# kondratchenko_telemetry_board.net
KiCad netlist of a schematic drawn in Altium Designer
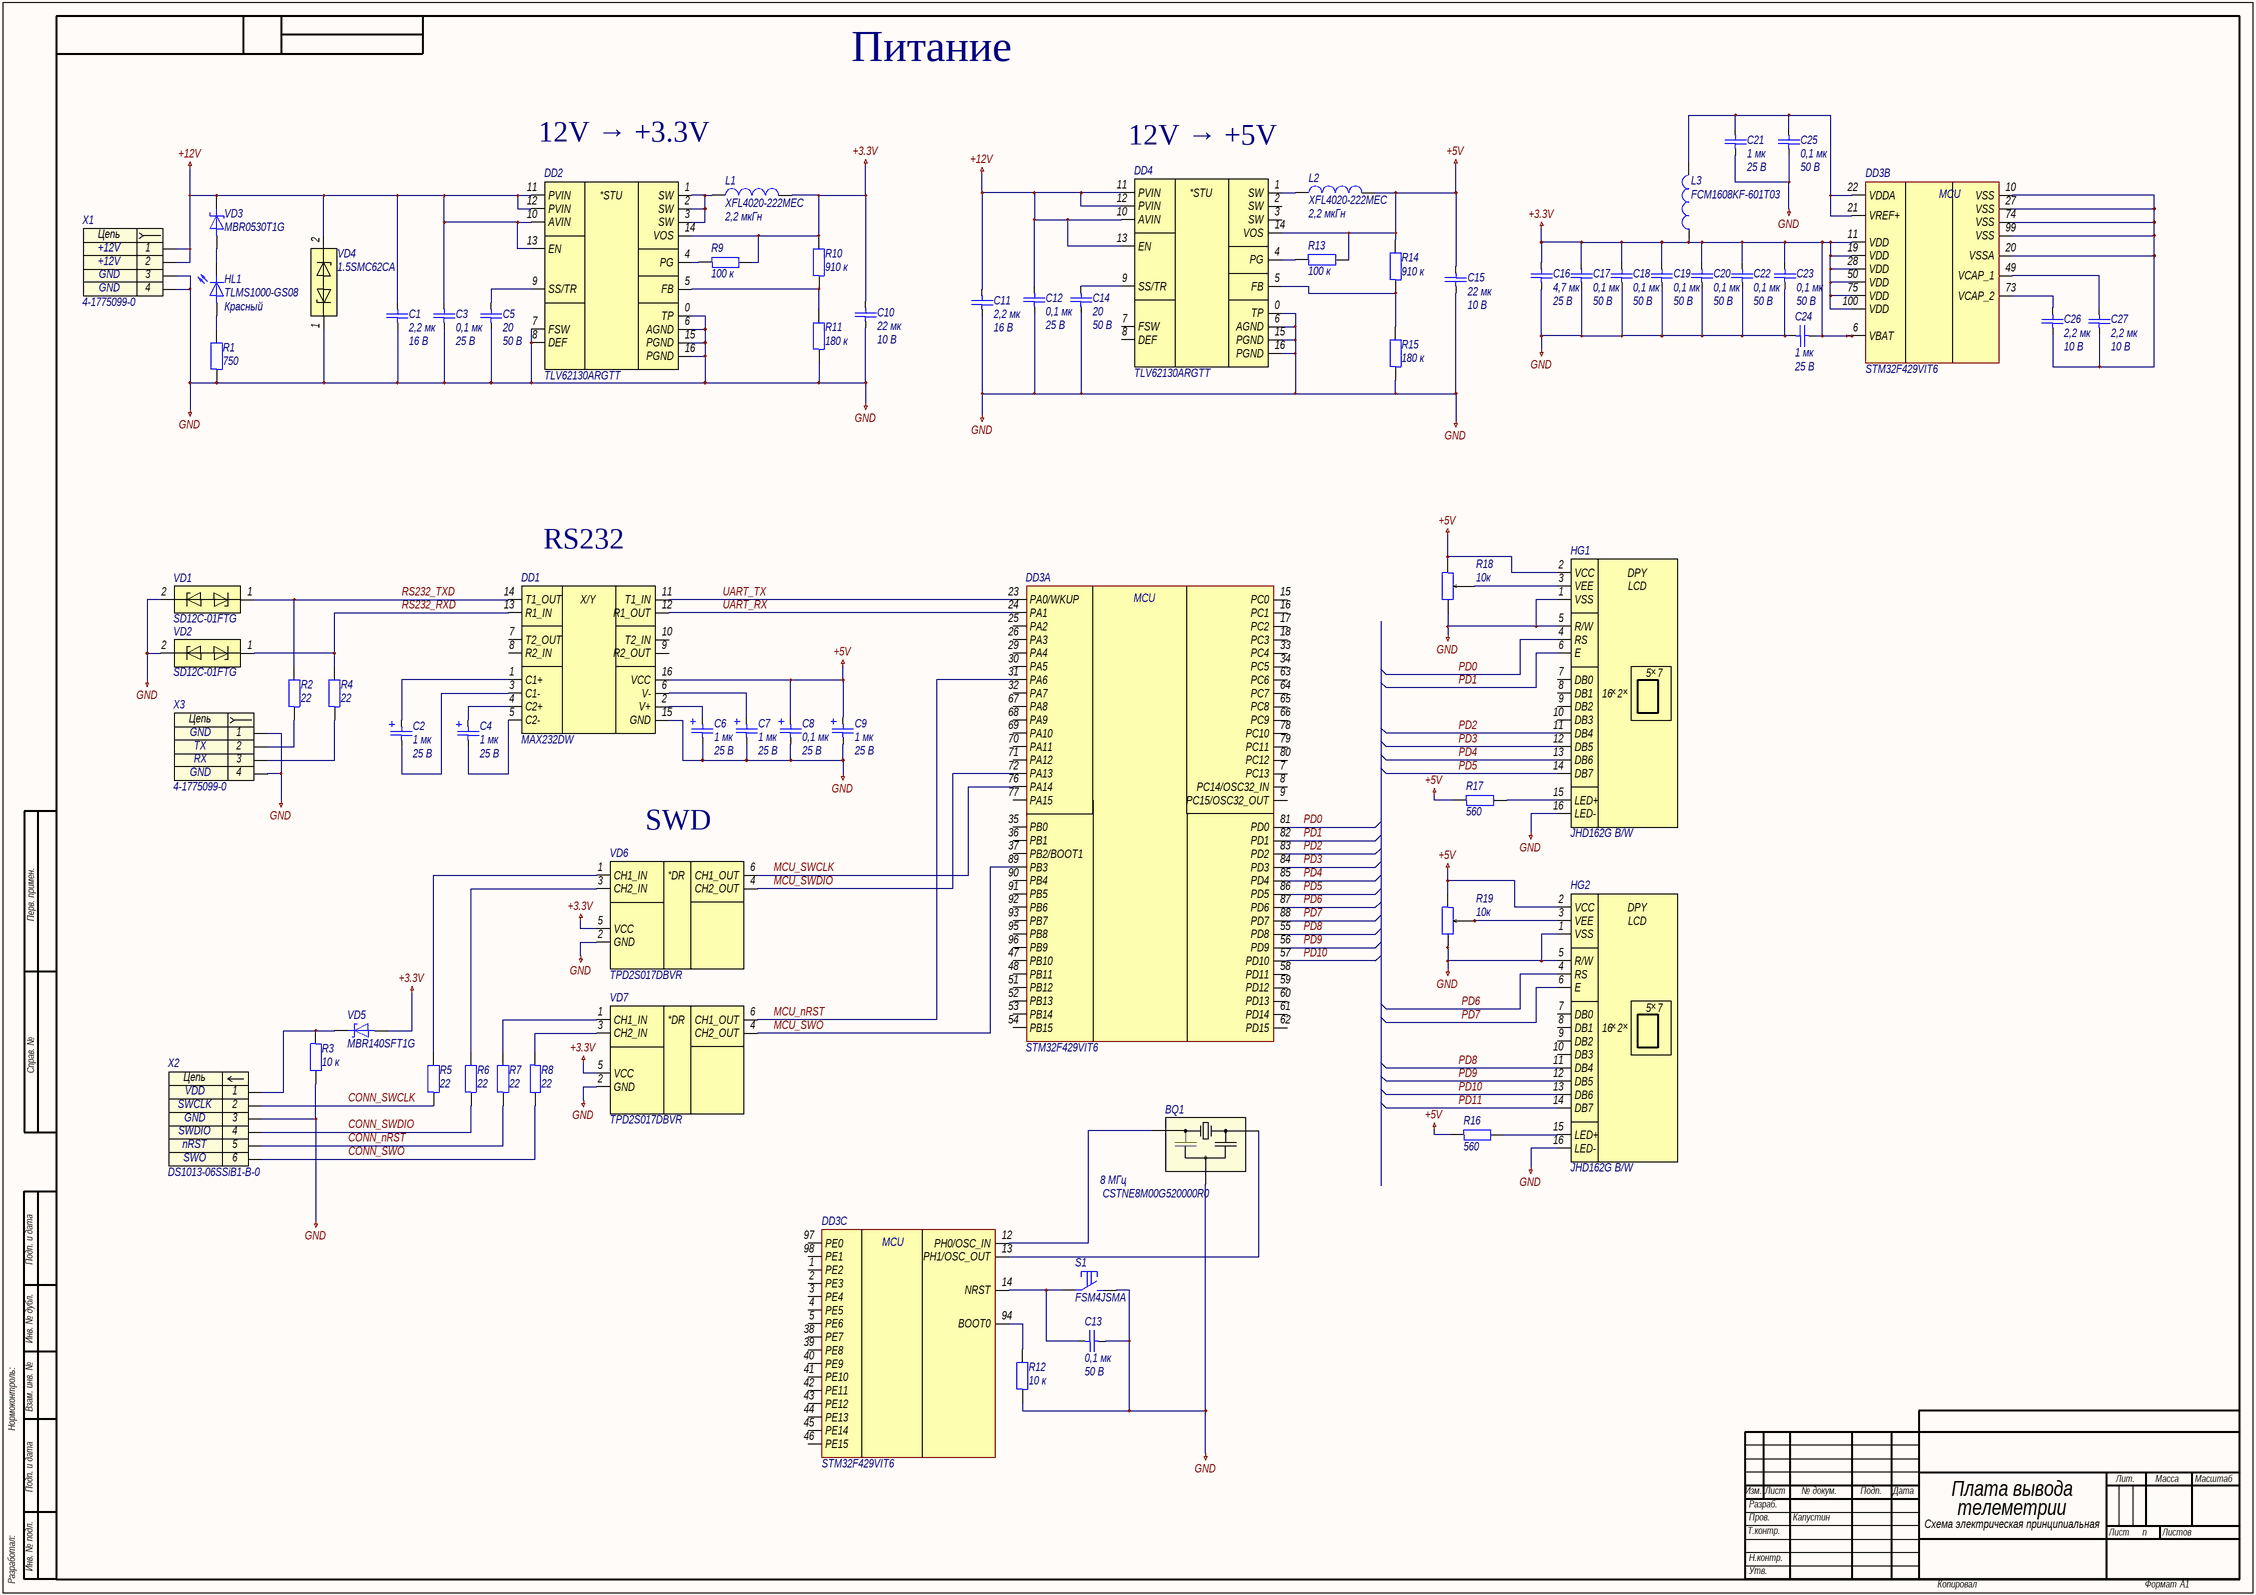
[diagram p0: kondratchenko_telemetry_board.SchDoc]

(export (version "E")
  (design (tool "Eeschema 10.0.6"))
  (components
    (comp (ref "BQ1")
      (value "CSTNE8M00G520000R0")
      (footprint "CSTCE-3-P120-320X130X70")
      (description "=Описание")
      (fields (field (name "ЧАСТОТA") "8 МГц"))
      (libsource (lib "Database_Students") (part "CSTNE8M00G520000R0"))
    )
    (comp (ref "C1")
      (value "2,2 мк")
      (footprint "C0603")
      (description "=Описание")
      (fields (field (name "НАПРЯЖЕНИЕ") "16 В"))
      (libsource (lib "Database_Students") (part "CAPACITOR-NONPOLAR"))
    )
    (comp (ref "C2")
      (value "1 мк")
      (footprint "C3216-18")
      (description "=Описание")
      (fields (field (name "НАПРЯЖЕНИЕ") "25 В"))
      (libsource (lib "Database_Students") (part "CAPACITOR-POLAR"))
    )
    (comp (ref "C3")
      (value "0,1 мк")
      (footprint "C0603")
      (description "=Описание")
      (fields (field (name "НАПРЯЖЕНИЕ") "25 В"))
      (libsource (lib "Database_Students") (part "CAPACITOR-NONPOLAR"))
    )
    (comp (ref "C4")
      (value "1 мк")
      (footprint "C3216-18")
      (description "=Описание")
      (fields (field (name "НАПРЯЖЕНИЕ") "25 В"))
      (libsource (lib "Database_Students") (part "CAPACITOR-POLAR"))
    )
    (comp (ref "C5")
      (value "20")
      (footprint "C0603")
      (description "=Описание")
      (fields (field (name "НАПРЯЖЕНИЕ") "50 В"))
      (libsource (lib "Database_Students") (part "CAPACITOR-NONPOLAR"))
    )
    (comp (ref "C6")
      (value "1 мк")
      (footprint "C3216-18")
      (description "=Описание")
      (fields (field (name "НАПРЯЖЕНИЕ") "25 В"))
      (libsource (lib "Database_Students") (part "CAPACITOR-POLAR"))
    )
    (comp (ref "C7")
      (value "1 мк")
      (footprint "C3216-18")
      (description "=Описание")
      (fields (field (name "НАПРЯЖЕНИЕ") "25 В"))
      (libsource (lib "Database_Students") (part "CAPACITOR-POLAR"))
    )
    (comp (ref "C8")
      (value "0,1 мк")
      (footprint "C3216-18")
      (description "=Описание")
      (fields (field (name "НАПРЯЖЕНИЕ") "25 В"))
      (libsource (lib "Database_Students") (part "CAPACITOR-POLAR"))
    )
    (comp (ref "C9")
      (value "1 мк")
      (footprint "C3216-18")
      (description "=Описание")
      (fields (field (name "НАПРЯЖЕНИЕ") "25 В"))
      (libsource (lib "Database_Students") (part "CAPACITOR-POLAR"))
    )
    (comp (ref "C10")
      (value "22 мк")
      (footprint "C1206")
      (description "=Описание")
      (fields (field (name "НАПРЯЖЕНИЕ") "10 В"))
      (libsource (lib "Database_Students") (part "CAPACITOR-NONPOLAR"))
    )
    (comp (ref "C11")
      (value "2,2 мк")
      (footprint "C0603")
      (description "=Описание")
      (fields (field (name "НАПРЯЖЕНИЕ") "16 В"))
      (libsource (lib "Database_Students") (part "CAPACITOR-NONPOLAR"))
    )
    (comp (ref "C12")
      (value "0,1 мк")
      (footprint "C0603")
      (description "=Описание")
      (fields (field (name "НАПРЯЖЕНИЕ") "25 В"))
      (libsource (lib "Database_Students") (part "CAPACITOR-NONPOLAR"))
    )
    (comp (ref "C13")
      (value "0,1 мк")
      (footprint "C0603")
      (description "=Описание")
      (fields (field (name "НАПРЯЖЕНИЕ") "50 В"))
      (libsource (lib "Database_Students") (part "CAPACITOR-NONPOLAR"))
    )
    (comp (ref "C14")
      (value "20")
      (footprint "C0603")
      (description "=Описание")
      (fields (field (name "НАПРЯЖЕНИЕ") "50 В"))
      (libsource (lib "Database_Students") (part "CAPACITOR-NONPOLAR"))
    )
    (comp (ref "C15")
      (value "22 мк")
      (footprint "C1206")
      (description "=Описание")
      (fields (field (name "НАПРЯЖЕНИЕ") "10 В"))
      (libsource (lib "Database_Students") (part "CAPACITOR-NONPOLAR"))
    )
    (comp (ref "C16")
      (value "4,7 мк")
      (footprint "C0603")
      (description "=Описание")
      (fields (field (name "НАПРЯЖЕНИЕ") "25 В"))
      (libsource (lib "Database_Students") (part "CAPACITOR-NONPOLAR"))
    )
    (comp (ref "C17")
      (value "0,1 мк")
      (footprint "C0603")
      (description "=Описание")
      (fields (field (name "НАПРЯЖЕНИЕ") "50 В"))
      (libsource (lib "Database_Students") (part "CAPACITOR-NONPOLAR"))
    )
    (comp (ref "C18")
      (value "0,1 мк")
      (footprint "C0603")
      (description "=Описание")
      (fields (field (name "НАПРЯЖЕНИЕ") "50 В"))
      (libsource (lib "Database_Students") (part "CAPACITOR-NONPOLAR"))
    )
    (comp (ref "C19")
      (value "0,1 мк")
      (footprint "C0603")
      (description "=Описание")
      (fields (field (name "НАПРЯЖЕНИЕ") "50 В"))
      (libsource (lib "Database_Students") (part "CAPACITOR-NONPOLAR"))
    )
    (comp (ref "C20")
      (value "0,1 мк")
      (footprint "C0603")
      (description "=Описание")
      (fields (field (name "НАПРЯЖЕНИЕ") "50 В"))
      (libsource (lib "Database_Students") (part "CAPACITOR-NONPOLAR"))
    )
    (comp (ref "C21")
      (value "1 мк")
      (footprint "C0603")
      (description "=Описание")
      (fields (field (name "НАПРЯЖЕНИЕ") "25 В"))
      (libsource (lib "Database_Students") (part "CAPACITOR-NONPOLAR"))
    )
    (comp (ref "C22")
      (value "0,1 мк")
      (footprint "C0603")
      (description "=Описание")
      (fields (field (name "НАПРЯЖЕНИЕ") "50 В"))
      (libsource (lib "Database_Students") (part "CAPACITOR-NONPOLAR"))
    )
    (comp (ref "C23")
      (value "0,1 мк")
      (footprint "C0603")
      (description "=Описание")
      (fields (field (name "НАПРЯЖЕНИЕ") "50 В"))
      (libsource (lib "Database_Students") (part "CAPACITOR-NONPOLAR"))
    )
    (comp (ref "C24")
      (value "1 мк")
      (footprint "C0603")
      (description "=Описание")
      (fields (field (name "НАПРЯЖЕНИЕ") "25 В"))
      (libsource (lib "Database_Students") (part "CAPACITOR-NONPOLAR"))
    )
    (comp (ref "C25")
      (value "0,1 мк")
      (footprint "C0603")
      (description "=Описание")
      (fields (field (name "НАПРЯЖЕНИЕ") "50 В"))
      (libsource (lib "Database_Students") (part "CAPACITOR-NONPOLAR"))
    )
    (comp (ref "C26")
      (value "2,2 мк")
      (footprint "C0603")
      (description "=Описание")
      (fields (field (name "НАПРЯЖЕНИЕ") "10 В"))
      (libsource (lib "Database_Students") (part "CAPACITOR-NONPOLAR"))
    )
    (comp (ref "C27")
      (value "2,2 мк")
      (footprint "C0603")
      (description "=Описание")
      (fields (field (name "НАПРЯЖЕНИЕ") "10 В"))
      (libsource (lib "Database_Students") (part "CAPACITOR-NONPOLAR"))
    )
    (comp (ref "DD1")
      (value "MAX232DW")
      (footprint "SOIC-16-P127-1030X750X265-L84X41")
      (description "=Описание")
      (libsource (lib "Database_Students") (part "MAX232DW"))
    )
    (comp (ref "DD2")
      (value "TLV62130ARGTT")
      (footprint "WQFN-16-P50-300X300X100-L40X24-T168X168")
      (description "=Описание")
      (libsource (lib "Database_Students") (part "TLV62130ARGTT"))
    )
    (comp (ref "DD3")
      (value "STM32F429VIT6")
      (footprint "LQFP-100-P50-1400X1400X160-L60X22")
      (description "=Описание")
      (libsource (lib "") (part "STM32F429VIT6_1"))
    )
    (comp (ref "DD4")
      (value "TLV62130ARGTT")
      (footprint "WQFN-16-P50-300X300X100-L40X24-T168X168")
      (description "=Описание")
      (libsource (lib "Database_Students") (part "TLV62130ARGTT"))
    )
    (comp (ref "HG1")
      (value "JHD162G B/W")
      (footprint "JHD162G B/W")
      (description "=Описание")
      (libsource (lib "Database_Students") (part "JHD162G B/W"))
    )
    (comp (ref "HG2")
      (value "JHD162G B/W")
      (footprint "JHD162G B/W")
      (description "=Описание")
      (libsource (lib "Database_Students") (part "JHD162G B/W"))
    )
    (comp (ref "HL1")
      (value "TLMS1000-GS08")
      (footprint "HL0603")
      (description "=Описание")
      (fields (field (name "ЦВЕТ") "Красный"))
      (libsource (lib "Database_Students") (part "LED-COMMON"))
    )
    (comp (ref "L1")
      (value "XFL4020-222MEC")
      (footprint "XFL-2-400X400X210")
      (description "=Описание")
      (fields (field (name "ИНДУКТИВНОСТЬ") "2,2 мкГн"))
      (libsource (lib "Database_Students") (part "INDUCTOR-COMMON"))
    )
    (comp (ref "L2")
      (value "XFL4020-222MEC")
      (footprint "XFL-2-400X400X210")
      (description "=Описание")
      (fields (field (name "ИНДУКТИВНОСТЬ") "2,2 мкГн"))
      (libsource (lib "Database_Students") (part "INDUCTOR-COMMON"))
    )
    (comp (ref "L3")
      (value "FCM1608KF-601T03")
      (footprint "FCM-2-0603")
      (description "=Описание")
      (libsource (lib "Database_Students") (part "FERRITE-BEAD"))
    )
    (comp (ref "R1")
      (value "750")
      (footprint "R0603")
      (description "=Описание")
      (libsource (lib "Database_Students") (part "RESISTOR-COMMON"))
    )
    (comp (ref "R2")
      (value "22")
      (footprint "R0603")
      (description "=Описание")
      (libsource (lib "Database_Students") (part "RESISTOR-COMMON"))
    )
    (comp (ref "R3")
      (value "10 к")
      (footprint "R0603")
      (description "=Описание")
      (libsource (lib "Database_Students") (part "RESISTOR-COMMON"))
    )
    (comp (ref "R4")
      (value "22")
      (footprint "R0603")
      (description "=Описание")
      (libsource (lib "Database_Students") (part "RESISTOR-COMMON"))
    )
    (comp (ref "R5")
      (value "22")
      (footprint "R0603")
      (description "=Описание")
      (libsource (lib "Database_Students") (part "RESISTOR-COMMON"))
    )
    (comp (ref "R6")
      (value "22")
      (footprint "R0603")
      (description "=Описание")
      (libsource (lib "Database_Students") (part "RESISTOR-COMMON"))
    )
    (comp (ref "R7")
      (value "22")
      (footprint "R0603")
      (description "=Описание")
      (libsource (lib "Database_Students") (part "RESISTOR-COMMON"))
    )
    (comp (ref "R8")
      (value "22")
      (footprint "R0603")
      (description "=Описание")
      (libsource (lib "Database_Students") (part "RESISTOR-COMMON"))
    )
    (comp (ref "R9")
      (value "100 к")
      (footprint "R0603")
      (description "=Описание")
      (libsource (lib "Database_Students") (part "RESISTOR-COMMON"))
    )
    (comp (ref "R10")
      (value "910 к")
      (footprint "R0603")
      (description "=Описание")
      (libsource (lib "Database_Students") (part "RESISTOR-COMMON"))
    )
    (comp (ref "R11")
      (value "180 к")
      (footprint "R0603")
      (description "=Описание")
      (libsource (lib "Database_Students") (part "RESISTOR-COMMON"))
    )
    (comp (ref "R12")
      (value "10 к")
      (footprint "R0603")
      (description "=Описание")
      (libsource (lib "Database_Students") (part "RESISTOR-COMMON"))
    )
    (comp (ref "R13")
      (value "100 к")
      (footprint "R0603")
      (description "=Описание")
      (libsource (lib "Database_Students") (part "RESISTOR-COMMON"))
    )
    (comp (ref "R14")
      (value "910 к")
      (footprint "R0603")
      (description "=Описание")
      (libsource (lib "Database_Students") (part "RESISTOR-COMMON"))
    )
    (comp (ref "R15")
      (value "180 к")
      (footprint "R0603")
      (description "=Описание")
      (libsource (lib "Database_Students") (part "RESISTOR-COMMON"))
    )
    (comp (ref "R16")
      (value "560")
      (footprint "R0603")
      (description "=Описание")
      (libsource (lib "Database_Students") (part "RESISTOR-COMMON"))
    )
    (comp (ref "R17")
      (value "560")
      (footprint "R0603")
      (description "=Описание")
      (libsource (lib "Database_Students") (part "RESISTOR-COMMON"))
    )
    (comp (ref "R18")
      (value "10к")
      (footprint "R3362")
      (description "=Описание")
      (libsource (lib "Database_Students") (part "TRIMMER-COMMON"))
    )
    (comp (ref "R19")
      (value "10к")
      (footprint "R3362")
      (description "=Описание")
      (libsource (lib "Database_Students") (part "TRIMMER-COMMON"))
    )
    (comp (ref "S1")
      (value "FSM4JSMA")
      (footprint "FSM4JSMA")
      (description "=Описание")
      (libsource (lib "Database_Students") (part "BUTTON"))
    )
    (comp (ref "VD1")
      (value "SD12C-01FTG")
      (footprint "SOD-323-257X130X114")
      (description "=Описание")
      (libsource (lib "") (part "ZENER-BI-DIRECTIONAL_1"))
    )
    (comp (ref "VD2")
      (value "SD12C-01FTG")
      (footprint "SOD-323-257X130X114")
      (description "=Описание")
      (libsource (lib "") (part "ZENER-BI-DIRECTIONAL_1"))
    )
    (comp (ref "VD3")
      (value "MBR0530T1G")
      (footprint "SOD-123-368X160X135")
      (description "=Описание")
      (libsource (lib "Database_Students") (part "DIODE-SCHOTTKY"))
    )
    (comp (ref "VD4")
      (value "1.5SMC62CA")
      (footprint "DO-214AB-790X590X262")
      (description "=Описание")
      (libsource (lib "Database_Students") (part "ZENER-BI-DIRECTIONAL"))
    )
    (comp (ref "VD5")
      (value "MBR140SFT1G")
      (footprint "SOD-123FL-370X165X98")
      (description "=Описание")
      (libsource (lib "Database_Students") (part "DIODE-SCHOTTKY"))
    )
    (comp (ref "VD6")
      (value "TPD2S017DBVR")
      (footprint "SOT-23-6-P95-290X280X145")
      (description "=Описание")
      (libsource (lib "Database_Students") (part "TPD2S017DBVR"))
    )
    (comp (ref "VD7")
      (value "TPD2S017DBVR")
      (footprint "SOT-23-6-P95-290X280X145")
      (description "=Описание")
      (libsource (lib "Database_Students") (part "TPD2S017DBVR"))
    )
    (comp (ref "X1")
      (value "4-1775099-0")
      (footprint "4-1775099-0")
      (description "=Описание")
      (libsource (lib "Database_Students") (part "HEADER-4-SCT"))
    )
    (comp (ref "X2")
      (value "DS1013-06SSiB1-B-0")
      (footprint "DS1013-06SSiB1-B-0")
      (description "=Описание")
      (libsource (lib "Database_Students") (part "HEADER-6-PLG"))
    )
    (comp (ref "X3")
      (value "4-1775099-0")
      (footprint "4-1775099-0")
      (description "=Описание")
      (libsource (lib "Database_Students") (part "HEADER-4-SCT"))
    )
  )
  (nets
    (net (code "1") (name "+3.3V") (class "Default")
      (node (ref "C10") (pin "1") (pinfunction "1_1") (pintype "passive"))
      (node (ref "C16") (pin "1") (pinfunction "1_1") (pintype "passive"))
      (node (ref "C17") (pin "1") (pinfunction "1_1") (pintype "passive"))
      (node (ref "C18") (pin "1") (pinfunction "1_1") (pintype "passive"))
      (node (ref "C19") (pin "1") (pinfunction "1_1") (pintype "passive"))
      (node (ref "C20") (pin "1") (pinfunction "1_1") (pintype "passive"))
      (node (ref "C22") (pin "1") (pinfunction "1_1") (pintype "passive"))
      (node (ref "C23") (pin "1") (pinfunction "1_1") (pintype "passive"))
      (node (ref "C24") (pin "1") (pinfunction "1_1") (pintype "passive"))
      (node (ref "DD2") (pin "14") (pinfunction "VOS_14") (pintype "passive"))
      (node (ref "DD3") (pin "100") (pinfunction "VDD_100") (pintype "passive"))
      (node (ref "DD3") (pin "11") (pinfunction "VDD_11") (pintype "passive"))
      (node (ref "DD3") (pin "19") (pinfunction "VDD_19") (pintype "passive"))
      (node (ref "DD3") (pin "28") (pinfunction "VDD_28") (pintype "passive"))
      (node (ref "DD3") (pin "50") (pinfunction "VDD_50") (pintype "passive"))
      (node (ref "DD3") (pin "6") (pinfunction "VBAT_6") (pintype "passive"))
      (node (ref "DD3") (pin "75") (pinfunction "VDD_75") (pintype "passive"))
      (node (ref "L1") (pin "2") (pinfunction "2_2") (pintype "passive"))
      (node (ref "L3") (pin "1") (pinfunction "1_1") (pintype "passive"))
      (node (ref "R10") (pin "2") (pinfunction "2_2") (pintype "passive"))
      (node (ref "R9") (pin "2") (pinfunction "2_2") (pintype "passive"))
      (node (ref "VD5") (pin "2") (pinfunction "2_2") (pintype "passive"))
      (node (ref "VD6") (pin "5") (pinfunction "VCC_5") (pintype "passive"))
      (node (ref "VD7") (pin "5") (pinfunction "VCC_5") (pintype "passive"))
    )
    (net (code "2") (name "+5V") (class "Default")
      (node (ref "C15") (pin "2") (pinfunction "2_2") (pintype "passive"))
      (node (ref "C8") (pin "1") (pinfunction "1_1") (pintype "passive"))
      (node (ref "C9") (pin "1") (pinfunction "1_1") (pintype "passive"))
      (node (ref "DD1") (pin "16") (pinfunction "VCC_16") (pintype "passive"))
      (node (ref "DD4") (pin "14") (pinfunction "VOS_14") (pintype "passive"))
      (node (ref "HG1") (pin "2") (pinfunction "VCC_2") (pintype "passive"))
      (node (ref "HG2") (pin "2") (pinfunction "VCC_2") (pintype "passive"))
      (node (ref "L2") (pin "2") (pinfunction "2_2") (pintype "passive"))
      (node (ref "R13") (pin "2") (pinfunction "2_2") (pintype "passive"))
      (node (ref "R14") (pin "2") (pinfunction "2_2") (pintype "passive"))
      (node (ref "R16") (pin "1") (pinfunction "1_1") (pintype "passive"))
      (node (ref "R17") (pin "1") (pinfunction "1_1") (pintype "passive"))
      (node (ref "R18") (pin "1") (pinfunction "1_1") (pintype "passive"))
      (node (ref "R19") (pin "1") (pinfunction "1_1") (pintype "passive"))
    )
    (net (code "3") (name "+12V") (class "Default")
      (node (ref "C1") (pin "1") (pinfunction "1_1") (pintype "passive"))
      (node (ref "C11") (pin "1") (pinfunction "1_1") (pintype "passive"))
      (node (ref "C12") (pin "1") (pinfunction "1_1") (pintype "passive"))
      (node (ref "C3") (pin "1") (pinfunction "1_1") (pintype "passive"))
      (node (ref "DD2") (pin "10") (pinfunction "AVIN_10") (pintype "passive"))
      (node (ref "DD2") (pin "11") (pinfunction "PVIN_11") (pintype "passive"))
      (node (ref "DD2") (pin "12") (pinfunction "PVIN_12") (pintype "passive"))
      (node (ref "DD2") (pin "13") (pinfunction "EN_13") (pintype "passive"))
      (node (ref "DD4") (pin "10") (pinfunction "AVIN_10") (pintype "passive"))
      (node (ref "DD4") (pin "11") (pinfunction "PVIN_11") (pintype "passive"))
      (node (ref "DD4") (pin "12") (pinfunction "PVIN_12") (pintype "passive"))
      (node (ref "DD4") (pin "13") (pinfunction "EN_13") (pintype "passive"))
      (node (ref "VD3") (pin "1") (pinfunction "1_1") (pintype "passive"))
      (node (ref "VD4") (pin "2") (pinfunction "2_2") (pintype "passive"))
      (node (ref "X1") (pin "1") (pinfunction "1_1") (pintype "passive"))
      (node (ref "X1") (pin "2") (pinfunction "2_2") (pintype "passive"))
    )
    (net (code "4") (name "/CONN_SWCLK") (class "Default")
      (node (ref "R5") (pin "1") (pinfunction "1_1") (pintype "passive"))
      (node (ref "X2") (pin "2") (pinfunction "2_2") (pintype "passive"))
    )
    (net (code "5") (name "/CONN_SWDIO") (class "Default")
      (node (ref "R6") (pin "1") (pinfunction "1_1") (pintype "passive"))
      (node (ref "X2") (pin "4") (pinfunction "4_4") (pintype "passive"))
    )
    (net (code "6") (name "/CONN_SWO") (class "Default")
      (node (ref "R8") (pin "2") (pinfunction "2_2") (pintype "passive"))
      (node (ref "X2") (pin "6") (pinfunction "6_6") (pintype "passive"))
    )
    (net (code "7") (name "/CONN_nRST") (class "Default")
      (node (ref "R7") (pin "1") (pinfunction "1_1") (pintype "passive"))
      (node (ref "X2") (pin "5") (pinfunction "5_5") (pintype "passive"))
    )
    (net (code "8") (name "/MCU_SWCLK") (class "Default")
      (node (ref "DD3") (pin "76") (pinfunction "PA14_76") (pintype "passive"))
      (node (ref "VD6") (pin "6") (pinfunction "CH1_OUT_6") (pintype "passive"))
    )
    (net (code "9") (name "/MCU_SWDIO") (class "Default")
      (node (ref "DD3") (pin "72") (pinfunction "PA13_72") (pintype "passive"))
      (node (ref "VD6") (pin "4") (pinfunction "CH2_OUT_4") (pintype "passive"))
    )
    (net (code "10") (name "/MCU_SWO") (class "Default")
      (node (ref "DD3") (pin "89") (pinfunction "PB3_89") (pintype "passive"))
      (node (ref "VD7") (pin "4") (pinfunction "CH2_OUT_4") (pintype "passive"))
    )
    (net (code "11") (name "/MCU_nRST") (class "Default")
      (node (ref "DD3") (pin "31") (pinfunction "PA6_31") (pintype "passive"))
      (node (ref "VD7") (pin "6") (pinfunction "CH1_OUT_6") (pintype "passive"))
    )
    (net (code "12") (name "/PD0") (class "Default")
      (node (ref "DD3") (pin "81") (pinfunction "PD0_81") (pintype "passive"))
      (node (ref "HG1") (pin "4") (pinfunction "RS_4") (pintype "passive"))
    )
    (net (code "13") (name "/PD1") (class "Default")
      (node (ref "DD3") (pin "82") (pinfunction "PD1_82") (pintype "passive"))
      (node (ref "HG1") (pin "6") (pinfunction "E_6") (pintype "passive"))
    )
    (net (code "14") (name "/PD2") (class "Default")
      (node (ref "DD3") (pin "83") (pinfunction "PD2_83") (pintype "passive"))
      (node (ref "HG1") (pin "11") (pinfunction "DB4_11") (pintype "passive"))
    )
    (net (code "15") (name "/PD3") (class "Default")
      (node (ref "DD3") (pin "84") (pinfunction "PD3_84") (pintype "passive"))
      (node (ref "HG1") (pin "12") (pinfunction "DB5_12") (pintype "passive"))
    )
    (net (code "16") (name "/PD4") (class "Default")
      (node (ref "DD3") (pin "85") (pinfunction "PD4_85") (pintype "passive"))
      (node (ref "HG1") (pin "13") (pinfunction "DB6_13") (pintype "passive"))
    )
    (net (code "17") (name "/PD5") (class "Default")
      (node (ref "DD3") (pin "86") (pinfunction "PD5_86") (pintype "passive"))
      (node (ref "HG1") (pin "14") (pinfunction "DB7_14") (pintype "passive"))
    )
    (net (code "18") (name "/PD6") (class "Default")
      (node (ref "DD3") (pin "87") (pinfunction "PD6_87") (pintype "passive"))
      (node (ref "HG2") (pin "4") (pinfunction "RS_4") (pintype "passive"))
    )
    (net (code "19") (name "/PD7") (class "Default")
      (node (ref "DD3") (pin "88") (pinfunction "PD7_88") (pintype "passive"))
      (node (ref "HG2") (pin "6") (pinfunction "E_6") (pintype "passive"))
    )
    (net (code "20") (name "/PD8") (class "Default")
      (node (ref "DD3") (pin "55") (pinfunction "PD8_55") (pintype "passive"))
      (node (ref "HG2") (pin "11") (pinfunction "DB4_11") (pintype "passive"))
    )
    (net (code "21") (name "/PD9") (class "Default")
      (node (ref "DD3") (pin "56") (pinfunction "PD9_56") (pintype "passive"))
      (node (ref "HG2") (pin "12") (pinfunction "DB5_12") (pintype "passive"))
    )
    (net (code "22") (name "/PD10") (class "Default")
      (node (ref "DD3") (pin "57") (pinfunction "PD10_57") (pintype "passive"))
      (node (ref "HG2") (pin "13") (pinfunction "DB6_13") (pintype "passive"))
    )
    (net (code "23") (name "/PD11") (class "Default")
      (node (ref "HG2") (pin "14") (pinfunction "DB7_14") (pintype "passive"))
    )
    (net (code "24") (name "/RS232_RXD") (class "Default")
      (node (ref "DD1") (pin "13") (pinfunction "R1_IN_13") (pintype "passive"))
      (node (ref "R4") (pin "2") (pinfunction "2_2") (pintype "passive"))
      (node (ref "VD2") (pin "1") (pinfunction "1_1") (pintype "passive"))
    )
    (net (code "25") (name "/RS232_TXD") (class "Default")
      (node (ref "DD1") (pin "14") (pinfunction "T1_OUT_14") (pintype "passive"))
      (node (ref "R2") (pin "2") (pinfunction "2_2") (pintype "passive"))
      (node (ref "VD1") (pin "1") (pinfunction "1_1") (pintype "passive"))
    )
    (net (code "26") (name "/UART_RX") (class "Default")
      (node (ref "DD1") (pin "12") (pinfunction "R1_OUT_12") (pintype "passive"))
      (node (ref "DD3") (pin "24") (pinfunction "PA1_24") (pintype "passive"))
    )
    (net (code "27") (name "/UART_TX") (class "Default")
      (node (ref "DD1") (pin "11") (pinfunction "T1_IN_11") (pintype "passive"))
      (node (ref "DD3") (pin "23") (pinfunction "PA0/WKUP_23") (pintype "passive"))
    )
    (net (code "28") (name "GND") (class "Default")
      (node (ref "BQ1") (pin "2") (pinfunction "2_2") (pintype "passive"))
      (node (ref "C1") (pin "2") (pinfunction "2_2") (pintype "passive"))
      (node (ref "C10") (pin "2") (pinfunction "2_2") (pintype "passive"))
      (node (ref "C11") (pin "2") (pinfunction "2_2") (pintype "passive"))
      (node (ref "C12") (pin "2") (pinfunction "2_2") (pintype "passive"))
      (node (ref "C13") (pin "1") (pinfunction "1_1") (pintype "passive"))
      (node (ref "C14") (pin "2") (pinfunction "2_2") (pintype "passive"))
      (node (ref "C15") (pin "1") (pinfunction "1_1") (pintype "passive"))
      (node (ref "C16") (pin "2") (pinfunction "2_2") (pintype "passive"))
      (node (ref "C17") (pin "2") (pinfunction "2_2") (pintype "passive"))
      (node (ref "C18") (pin "2") (pinfunction "2_2") (pintype "passive"))
      (node (ref "C19") (pin "2") (pinfunction "2_2") (pintype "passive"))
      (node (ref "C20") (pin "2") (pinfunction "2_2") (pintype "passive"))
      (node (ref "C21") (pin "2") (pinfunction "2_2") (pintype "passive"))
      (node (ref "C22") (pin "2") (pinfunction "2_2") (pintype "passive"))
      (node (ref "C23") (pin "2") (pinfunction "2_2") (pintype "passive"))
      (node (ref "C24") (pin "2") (pinfunction "2_2") (pintype "passive"))
      (node (ref "C25") (pin "2") (pinfunction "2_2") (pintype "passive"))
      (node (ref "C3") (pin "2") (pinfunction "2_2") (pintype "passive"))
      (node (ref "C5") (pin "2") (pinfunction "2_2") (pintype "passive"))
      (node (ref "C6") (pin "2") (pinfunction "2_2") (pintype "passive"))
      (node (ref "C7") (pin "2") (pinfunction "2_2") (pintype "passive"))
      (node (ref "C8") (pin "2") (pinfunction "2_2") (pintype "passive"))
      (node (ref "C9") (pin "2") (pinfunction "2_2") (pintype "passive"))
      (node (ref "DD1") (pin "15") (pinfunction "GND_15") (pintype "passive"))
      (node (ref "DD2") (pin "0") (pinfunction "TP_0") (pintype "passive"))
      (node (ref "DD2") (pin "15") (pinfunction "PGND_15") (pintype "passive"))
      (node (ref "DD2") (pin "16") (pinfunction "PGND_16") (pintype "passive"))
      (node (ref "DD2") (pin "6") (pinfunction "AGND_6") (pintype "passive"))
      (node (ref "DD2") (pin "7") (pinfunction "FSW_7") (pintype "passive"))
      (node (ref "DD2") (pin "8") (pinfunction "DEF_8") (pintype "passive"))
      (node (ref "DD4") (pin "0") (pinfunction "TP_0") (pintype "passive"))
      (node (ref "DD4") (pin "15") (pinfunction "PGND_15") (pintype "passive"))
      (node (ref "DD4") (pin "16") (pinfunction "PGND_16") (pintype "passive"))
      (node (ref "DD4") (pin "6") (pinfunction "AGND_6") (pintype "passive"))
      (node (ref "HG1") (pin "1") (pinfunction "VSS_1") (pintype "passive"))
      (node (ref "HG1") (pin "16") (pinfunction "LED-_16") (pintype "passive"))
      (node (ref "HG1") (pin "5") (pinfunction "R/W_5") (pintype "passive"))
      (node (ref "HG2") (pin "1") (pinfunction "VSS_1") (pintype "passive"))
      (node (ref "HG2") (pin "16") (pinfunction "LED-_16") (pintype "passive"))
      (node (ref "HG2") (pin "5") (pinfunction "R/W_5") (pintype "passive"))
      (node (ref "R1") (pin "1") (pinfunction "1_1") (pintype "passive"))
      (node (ref "R11") (pin "1") (pinfunction "1_1") (pintype "passive"))
      (node (ref "R12") (pin "1") (pinfunction "1_1") (pintype "passive"))
      (node (ref "R15") (pin "1") (pinfunction "1_1") (pintype "passive"))
      (node (ref "R18") (pin "3") (pinfunction "3_3") (pintype "passive"))
      (node (ref "R19") (pin "3") (pinfunction "3_3") (pintype "passive"))
      (node (ref "R3") (pin "2") (pinfunction "2_2") (pintype "passive"))
      (node (ref "S1") (pin "2") (pinfunction "2_2") (pintype "passive"))
      (node (ref "VD1") (pin "2") (pinfunction "2_2") (pintype "passive"))
      (node (ref "VD2") (pin "2") (pinfunction "2_2") (pintype "passive"))
      (node (ref "VD4") (pin "1") (pinfunction "1_1") (pintype "passive"))
      (node (ref "VD6") (pin "2") (pinfunction "GND_2") (pintype "passive"))
      (node (ref "VD7") (pin "2") (pinfunction "GND_2") (pintype "passive"))
      (node (ref "X1") (pin "3") (pinfunction "3_3") (pintype "passive"))
      (node (ref "X1") (pin "4") (pinfunction "4_4") (pintype "passive"))
      (node (ref "X2") (pin "3") (pinfunction "3_3") (pintype "passive"))
      (node (ref "X3") (pin "1") (pinfunction "1_1") (pintype "passive"))
      (node (ref "X3") (pin "4") (pinfunction "4_4") (pintype "passive"))
    )
    (net (code "29") (name "Net-(DD1-C1+)") (class "Default")
      (node (ref "C2") (pin "1") (pinfunction "1_1") (pintype "passive"))
      (node (ref "DD1") (pin "1") (pinfunction "C1+_1") (pintype "passive"))
    )
    (net (code "30") (name "Net-(DD1-C1-)") (class "Default")
      (node (ref "C2") (pin "2") (pinfunction "2_2") (pintype "passive"))
      (node (ref "DD1") (pin "3") (pinfunction "C1-_3") (pintype "passive"))
    )
    (net (code "31") (name "Net-(DD1-C2+)") (class "Default")
      (node (ref "C4") (pin "1") (pinfunction "1_1") (pintype "passive"))
      (node (ref "DD1") (pin "4") (pinfunction "C2+_4") (pintype "passive"))
    )
    (net (code "32") (name "Net-(DD1-C2-)") (class "Default")
      (node (ref "C4") (pin "2") (pinfunction "2_2") (pintype "passive"))
      (node (ref "DD1") (pin "5") (pinfunction "C2-_5") (pintype "passive"))
    )
    (net (code "33") (name "Net-(DD1-V+)") (class "Default")
      (node (ref "C6") (pin "1") (pinfunction "1_1") (pintype "passive"))
      (node (ref "DD1") (pin "2") (pinfunction "V+_2") (pintype "passive"))
    )
    (net (code "34") (name "Net-(DD1-V-)") (class "Default")
      (node (ref "C7") (pin "1") (pinfunction "1_1") (pintype "passive"))
      (node (ref "DD1") (pin "6") (pinfunction "V-_6") (pintype "passive"))
    )
    (net (code "35") (name "Net-(DD2-FB)") (class "Default")
      (node (ref "DD2") (pin "5") (pinfunction "FB_5") (pintype "passive"))
      (node (ref "R10") (pin "1") (pinfunction "1_1") (pintype "passive"))
      (node (ref "R11") (pin "2") (pinfunction "2_2") (pintype "passive"))
    )
    (net (code "36") (name "Net-(DD2-PG)") (class "Default")
      (node (ref "DD2") (pin "4") (pinfunction "PG_4") (pintype "passive"))
      (node (ref "R9") (pin "1") (pinfunction "1_1") (pintype "passive"))
    )
    (net (code "37") (name "Net-(DD2-SS{slash}TR)") (class "Default")
      (node (ref "C5") (pin "1") (pinfunction "1_1") (pintype "passive"))
      (node (ref "DD2") (pin "9") (pinfunction "SS/TR_9") (pintype "passive"))
    )
    (net (code "38") (name "Net-(DD2-SW-Pad1)") (class "Default")
      (node (ref "DD2") (pin "1") (pinfunction "SW_1") (pintype "passive"))
      (node (ref "DD2") (pin "2") (pinfunction "SW_2") (pintype "passive"))
      (node (ref "DD2") (pin "3") (pinfunction "SW_3") (pintype "passive"))
      (node (ref "L1") (pin "1") (pinfunction "1_1") (pintype "passive"))
    )
    (net (code "39") (name "Net-(DD3B-VCAP_1)") (class "Default")
      (node (ref "C27") (pin "1") (pinfunction "1_1") (pintype "passive"))
      (node (ref "DD3") (pin "49") (pinfunction "VCAP_1_49") (pintype "passive"))
    )
    (net (code "40") (name "Net-(DD3B-VCAP_2)") (class "Default")
      (node (ref "C26") (pin "1") (pinfunction "1_1") (pintype "passive"))
      (node (ref "DD3") (pin "73") (pinfunction "VCAP_2_73") (pintype "passive"))
    )
    (net (code "41") (name "Net-(DD3B-VDDA)") (class "Default")
      (node (ref "C21") (pin "1") (pinfunction "1_1") (pintype "passive"))
      (node (ref "C25") (pin "1") (pinfunction "1_1") (pintype "passive"))
      (node (ref "DD3") (pin "21") (pinfunction "VREF+_21") (pintype "passive"))
      (node (ref "DD3") (pin "22") (pinfunction "VDDA_22") (pintype "passive"))
      (node (ref "L3") (pin "2") (pinfunction "2_2") (pintype "passive"))
    )
    (net (code "42") (name "Net-(DD3B-VSSA)") (class "Default")
      (node (ref "C26") (pin "2") (pinfunction "2_2") (pintype "passive"))
      (node (ref "C27") (pin "2") (pinfunction "2_2") (pintype "passive"))
      (node (ref "DD3") (pin "10") (pinfunction "VSS_10") (pintype "passive"))
      (node (ref "DD3") (pin "20") (pinfunction "VSSA_20") (pintype "passive"))
      (node (ref "DD3") (pin "27") (pinfunction "VSS_27") (pintype "passive"))
      (node (ref "DD3") (pin "74") (pinfunction "VSS_74") (pintype "passive"))
      (node (ref "DD3") (pin "99") (pinfunction "VSS_99") (pintype "passive"))
    )
    (net (code "43") (name "Net-(DD3C-BOOT0)") (class "Default")
      (node (ref "DD3") (pin "94") (pinfunction "BOOT0_94") (pintype "passive"))
      (node (ref "R12") (pin "2") (pinfunction "2_2") (pintype "passive"))
    )
    (net (code "44") (name "Net-(DD3C-NRST)") (class "Default")
      (node (ref "C13") (pin "2") (pinfunction "2_2") (pintype "passive"))
      (node (ref "DD3") (pin "14") (pinfunction "NRST_14") (pintype "passive"))
      (node (ref "S1") (pin "1") (pinfunction "1_1") (pintype "passive"))
    )
    (net (code "45") (name "Net-(DD3C-PH0{slash}OSC_IN)") (class "Default")
      (node (ref "BQ1") (pin "3") (pinfunction "3_3") (pintype "passive"))
      (node (ref "DD3") (pin "12") (pinfunction "PH0/OSC_IN_12") (pintype "passive"))
    )
    (net (code "46") (name "Net-(DD3C-PH1{slash}OSC_OUT)") (class "Default")
      (node (ref "BQ1") (pin "1") (pinfunction "1_1") (pintype "passive"))
      (node (ref "DD3") (pin "13") (pinfunction "PH1/OSC_OUT_13") (pintype "passive"))
    )
    (net (code "47") (name "Net-(DD4-FB)") (class "Default")
      (node (ref "DD4") (pin "5") (pinfunction "FB_5") (pintype "passive"))
      (node (ref "R14") (pin "1") (pinfunction "1_1") (pintype "passive"))
      (node (ref "R15") (pin "2") (pinfunction "2_2") (pintype "passive"))
    )
    (net (code "48") (name "Net-(DD4-PG)") (class "Default")
      (node (ref "DD4") (pin "4") (pinfunction "PG_4") (pintype "passive"))
      (node (ref "R13") (pin "1") (pinfunction "1_1") (pintype "passive"))
    )
    (net (code "49") (name "Net-(DD4-SS{slash}TR)") (class "Default")
      (node (ref "C14") (pin "1") (pinfunction "1_1") (pintype "passive"))
      (node (ref "DD4") (pin "9") (pinfunction "SS/TR_9") (pintype "passive"))
    )
    (net (code "50") (name "Net-(DD4-SW-Pad1)") (class "Default")
      (node (ref "DD4") (pin "1") (pinfunction "SW_1") (pintype "passive"))
      (node (ref "L2") (pin "1") (pinfunction "1_1") (pintype "passive"))
    )
    (net (code "51") (name "Net-(HG1-LED+)") (class "Default")
      (node (ref "HG1") (pin "15") (pinfunction "LED+_15") (pintype "passive"))
      (node (ref "R17") (pin "2") (pinfunction "2_2") (pintype "passive"))
    )
    (net (code "52") (name "Net-(HG1-VEE)") (class "Default")
      (node (ref "HG1") (pin "3") (pinfunction "VEE_3") (pintype "passive"))
      (node (ref "R18") (pin "2") (pinfunction "2_2") (pintype "passive"))
    )
    (net (code "53") (name "Net-(HG2-LED+)") (class "Default")
      (node (ref "HG2") (pin "15") (pinfunction "LED+_15") (pintype "passive"))
      (node (ref "R16") (pin "2") (pinfunction "2_2") (pintype "passive"))
    )
    (net (code "54") (name "Net-(HG2-VEE)") (class "Default")
      (node (ref "HG2") (pin "3") (pinfunction "VEE_3") (pintype "passive"))
      (node (ref "R19") (pin "2") (pinfunction "2_2") (pintype "passive"))
    )
    (net (code "55") (name "Net-(HL1-Pad1)") (class "Default")
      (node (ref "HL1") (pin "1") (pinfunction "1_1") (pintype "passive"))
      (node (ref "VD3") (pin "2") (pinfunction "2_2") (pintype "passive"))
    )
    (net (code "56") (name "Net-(HL1-Pad2)") (class "Default")
      (node (ref "HL1") (pin "2") (pinfunction "2_2") (pintype "passive"))
      (node (ref "R1") (pin "2") (pinfunction "2_2") (pintype "passive"))
    )
    (net (code "57") (name "Net-(R2-Pad1)") (class "Default")
      (node (ref "R2") (pin "1") (pinfunction "1_1") (pintype "passive"))
      (node (ref "X3") (pin "2") (pinfunction "2_2") (pintype "passive"))
    )
    (net (code "58") (name "Net-(R3-Pad1)") (class "Default")
      (node (ref "R3") (pin "1") (pinfunction "1_1") (pintype "passive"))
      (node (ref "VD5") (pin "1") (pinfunction "1_1") (pintype "passive"))
      (node (ref "X2") (pin "1") (pinfunction "1_1") (pintype "passive"))
    )
    (net (code "59") (name "Net-(R4-Pad1)") (class "Default")
      (node (ref "R4") (pin "1") (pinfunction "1_1") (pintype "passive"))
      (node (ref "X3") (pin "3") (pinfunction "3_3") (pintype "passive"))
    )
    (net (code "60") (name "Net-(VD6-CH1_IN)") (class "Default")
      (node (ref "R5") (pin "2") (pinfunction "2_2") (pintype "passive"))
      (node (ref "VD6") (pin "1") (pinfunction "CH1_IN_1") (pintype "passive"))
    )
    (net (code "61") (name "Net-(VD6-CH2_IN)") (class "Default")
      (node (ref "R6") (pin "2") (pinfunction "2_2") (pintype "passive"))
      (node (ref "VD6") (pin "3") (pinfunction "CH2_IN_3") (pintype "passive"))
    )
    (net (code "62") (name "Net-(VD7-CH1_IN)") (class "Default")
      (node (ref "R7") (pin "2") (pinfunction "2_2") (pintype "passive"))
      (node (ref "VD7") (pin "1") (pinfunction "CH1_IN_1") (pintype "passive"))
    )
    (net (code "63") (name "Net-(VD7-CH2_IN)") (class "Default")
      (node (ref "R8") (pin "1") (pinfunction "1_1") (pintype "passive"))
      (node (ref "VD7") (pin "3") (pinfunction "CH2_IN_3") (pintype "passive"))
    )
    (net (code "64") (name "unconnected-(DD1-R2_IN-Pad8)") (class "Default")
      (node (ref "DD1") (pin "8") (pinfunction "R2_IN_8") (pintype "passive"))
    )
    (net (code "65") (name "unconnected-(DD1-R2_OUT-Pad9)") (class "Default")
      (node (ref "DD1") (pin "9") (pinfunction "R2_OUT_9") (pintype "passive"))
    )
    (net (code "66") (name "unconnected-(DD1-T2_IN-Pad10)") (class "Default")
      (node (ref "DD1") (pin "10") (pinfunction "T2_IN_10") (pintype "passive"))
    )
    (net (code "67") (name "unconnected-(DD1-T2_OUT-Pad7)") (class "Default")
      (node (ref "DD1") (pin "7") (pinfunction "T2_OUT_7") (pintype "passive"))
    )
    (net (code "68") (name "unconnected-(DD3A-PA2-Pad25)") (class "Default")
      (node (ref "DD3") (pin "25") (pinfunction "PA2_25") (pintype "passive"))
    )
    (net (code "69") (name "unconnected-(DD3A-PA3-Pad26)") (class "Default")
      (node (ref "DD3") (pin "26") (pinfunction "PA3_26") (pintype "passive"))
    )
    (net (code "70") (name "unconnected-(DD3A-PA4-Pad29)") (class "Default")
      (node (ref "DD3") (pin "29") (pinfunction "PA4_29") (pintype "passive"))
    )
    (net (code "71") (name "unconnected-(DD3A-PA5-Pad30)") (class "Default")
      (node (ref "DD3") (pin "30") (pinfunction "PA5_30") (pintype "passive"))
    )
    (net (code "72") (name "unconnected-(DD3A-PA7-Pad32)") (class "Default")
      (node (ref "DD3") (pin "32") (pinfunction "PA7_32") (pintype "passive"))
    )
    (net (code "73") (name "unconnected-(DD3A-PA8-Pad67)") (class "Default")
      (node (ref "DD3") (pin "67") (pinfunction "PA8_67") (pintype "passive"))
    )
    (net (code "74") (name "unconnected-(DD3A-PA9-Pad68)") (class "Default")
      (node (ref "DD3") (pin "68") (pinfunction "PA9_68") (pintype "passive"))
    )
    (net (code "75") (name "unconnected-(DD3A-PA10-Pad69)") (class "Default")
      (node (ref "DD3") (pin "69") (pinfunction "PA10_69") (pintype "passive"))
    )
    (net (code "76") (name "unconnected-(DD3A-PA11-Pad70)") (class "Default")
      (node (ref "DD3") (pin "70") (pinfunction "PA11_70") (pintype "passive"))
    )
    (net (code "77") (name "unconnected-(DD3A-PA12-Pad71)") (class "Default")
      (node (ref "DD3") (pin "71") (pinfunction "PA12_71") (pintype "passive"))
    )
    (net (code "78") (name "unconnected-(DD3A-PA15-Pad77)") (class "Default")
      (node (ref "DD3") (pin "77") (pinfunction "PA15_77") (pintype "passive"))
    )
    (net (code "79") (name "unconnected-(DD3A-PB0-Pad35)") (class "Default")
      (node (ref "DD3") (pin "35") (pinfunction "PB0_35") (pintype "passive"))
    )
    (net (code "80") (name "unconnected-(DD3A-PB1-Pad36)") (class "Default")
      (node (ref "DD3") (pin "36") (pinfunction "PB1_36") (pintype "passive"))
    )
    (net (code "81") (name "unconnected-(DD3A-PB2{slash}BOOT1-Pad37)") (class "Default")
      (node (ref "DD3") (pin "37") (pinfunction "PB2/BOOT1_37") (pintype "passive"))
    )
    (net (code "82") (name "unconnected-(DD3A-PB4-Pad90)") (class "Default")
      (node (ref "DD3") (pin "90") (pinfunction "PB4_90") (pintype "passive"))
    )
    (net (code "83") (name "unconnected-(DD3A-PB5-Pad91)") (class "Default")
      (node (ref "DD3") (pin "91") (pinfunction "PB5_91") (pintype "passive"))
    )
    (net (code "84") (name "unconnected-(DD3A-PB6-Pad92)") (class "Default")
      (node (ref "DD3") (pin "92") (pinfunction "PB6_92") (pintype "passive"))
    )
    (net (code "85") (name "unconnected-(DD3A-PB7-Pad93)") (class "Default")
      (node (ref "DD3") (pin "93") (pinfunction "PB7_93") (pintype "passive"))
    )
    (net (code "86") (name "unconnected-(DD3A-PB8-Pad95)") (class "Default")
      (node (ref "DD3") (pin "95") (pinfunction "PB8_95") (pintype "passive"))
    )
    (net (code "87") (name "unconnected-(DD3A-PB9-Pad96)") (class "Default")
      (node (ref "DD3") (pin "96") (pinfunction "PB9_96") (pintype "passive"))
    )
    (net (code "88") (name "unconnected-(DD3A-PB10-Pad47)") (class "Default")
      (node (ref "DD3") (pin "47") (pinfunction "PB10_47") (pintype "passive"))
    )
    (net (code "89") (name "unconnected-(DD3A-PB11-Pad48)") (class "Default")
      (node (ref "DD3") (pin "48") (pinfunction "PB11_48") (pintype "passive"))
    )
    (net (code "90") (name "unconnected-(DD3A-PB12-Pad51)") (class "Default")
      (node (ref "DD3") (pin "51") (pinfunction "PB12_51") (pintype "passive"))
    )
    (net (code "91") (name "unconnected-(DD3A-PB13-Pad52)") (class "Default")
      (node (ref "DD3") (pin "52") (pinfunction "PB13_52") (pintype "passive"))
    )
    (net (code "92") (name "unconnected-(DD3A-PB14-Pad53)") (class "Default")
      (node (ref "DD3") (pin "53") (pinfunction "PB14_53") (pintype "passive"))
    )
    (net (code "93") (name "unconnected-(DD3A-PB15-Pad54)") (class "Default")
      (node (ref "DD3") (pin "54") (pinfunction "PB15_54") (pintype "passive"))
    )
    (net (code "94") (name "unconnected-(DD3A-PC0-Pad15)") (class "Default")
      (node (ref "DD3") (pin "15") (pinfunction "PC0_15") (pintype "passive"))
    )
    (net (code "95") (name "unconnected-(DD3A-PC1-Pad16)") (class "Default")
      (node (ref "DD3") (pin "16") (pinfunction "PC1_16") (pintype "passive"))
    )
    (net (code "96") (name "unconnected-(DD3A-PC2-Pad17)") (class "Default")
      (node (ref "DD3") (pin "17") (pinfunction "PC2_17") (pintype "passive"))
    )
    (net (code "97") (name "unconnected-(DD3A-PC3-Pad18)") (class "Default")
      (node (ref "DD3") (pin "18") (pinfunction "PC3_18") (pintype "passive"))
    )
    (net (code "98") (name "unconnected-(DD3A-PC4-Pad33)") (class "Default")
      (node (ref "DD3") (pin "33") (pinfunction "PC4_33") (pintype "passive"))
    )
    (net (code "99") (name "unconnected-(DD3A-PC5-Pad34)") (class "Default")
      (node (ref "DD3") (pin "34") (pinfunction "PC5_34") (pintype "passive"))
    )
    (net (code "100") (name "unconnected-(DD3A-PC6-Pad63)") (class "Default")
      (node (ref "DD3") (pin "63") (pinfunction "PC6_63") (pintype "passive"))
    )
    (net (code "101") (name "unconnected-(DD3A-PC7-Pad64)") (class "Default")
      (node (ref "DD3") (pin "64") (pinfunction "PC7_64") (pintype "passive"))
    )
    (net (code "102") (name "unconnected-(DD3A-PC8-Pad65)") (class "Default")
      (node (ref "DD3") (pin "65") (pinfunction "PC8_65") (pintype "passive"))
    )
    (net (code "103") (name "unconnected-(DD3A-PC9-Pad66)") (class "Default")
      (node (ref "DD3") (pin "66") (pinfunction "PC9_66") (pintype "passive"))
    )
    (net (code "104") (name "unconnected-(DD3A-PC10-Pad78)") (class "Default")
      (node (ref "DD3") (pin "78") (pinfunction "PC10_78") (pintype "passive"))
    )
    (net (code "105") (name "unconnected-(DD3A-PC11-Pad79)") (class "Default")
      (node (ref "DD3") (pin "79") (pinfunction "PC11_79") (pintype "passive"))
    )
    (net (code "106") (name "unconnected-(DD3A-PC12-Pad80)") (class "Default")
      (node (ref "DD3") (pin "80") (pinfunction "PC12_80") (pintype "passive"))
    )
    (net (code "107") (name "unconnected-(DD3A-PC13-Pad7)") (class "Default")
      (node (ref "DD3") (pin "7") (pinfunction "PC13_7") (pintype "passive"))
    )
    (net (code "108") (name "unconnected-(DD3A-PC14{slash}OSC32_IN-Pad8)") (class "Default")
      (node (ref "DD3") (pin "8") (pinfunction "PC14/OSC32_IN_8") (pintype "passive"))
    )
    (net (code "109") (name "unconnected-(DD3A-PC15{slash}OSC32_OUT-Pad9)") (class "Default")
      (node (ref "DD3") (pin "9") (pinfunction "PC15/OSC32_OUT_9") (pintype "passive"))
    )
    (net (code "110") (name "unconnected-(DD3A-PD11-Pad58)") (class "Default")
      (node (ref "DD3") (pin "58") (pinfunction "PD11_58") (pintype "passive"))
    )
    (net (code "111") (name "unconnected-(DD3A-PD12-Pad59)") (class "Default")
      (node (ref "DD3") (pin "59") (pinfunction "PD12_59") (pintype "passive"))
    )
    (net (code "112") (name "unconnected-(DD3A-PD13-Pad60)") (class "Default")
      (node (ref "DD3") (pin "60") (pinfunction "PD13_60") (pintype "passive"))
    )
    (net (code "113") (name "unconnected-(DD3A-PD14-Pad61)") (class "Default")
      (node (ref "DD3") (pin "61") (pinfunction "PD14_61") (pintype "passive"))
    )
    (net (code "114") (name "unconnected-(DD3A-PD15-Pad62)") (class "Default")
      (node (ref "DD3") (pin "62") (pinfunction "PD15_62") (pintype "passive"))
    )
    (net (code "115") (name "unconnected-(DD3C-PE0-Pad97)") (class "Default")
      (node (ref "DD3") (pin "97") (pinfunction "PE0_97") (pintype "passive"))
    )
    (net (code "116") (name "unconnected-(DD3C-PE1-Pad98)") (class "Default")
      (node (ref "DD3") (pin "98") (pinfunction "PE1_98") (pintype "passive"))
    )
    (net (code "117") (name "unconnected-(DD3C-PE2-Pad1)") (class "Default")
      (node (ref "DD3") (pin "1") (pinfunction "PE2_1") (pintype "passive"))
    )
    (net (code "118") (name "unconnected-(DD3C-PE3-Pad2)") (class "Default")
      (node (ref "DD3") (pin "2") (pinfunction "PE3_2") (pintype "passive"))
    )
    (net (code "119") (name "unconnected-(DD3C-PE4-Pad3)") (class "Default")
      (node (ref "DD3") (pin "3") (pinfunction "PE4_3") (pintype "passive"))
    )
    (net (code "120") (name "unconnected-(DD3C-PE5-Pad4)") (class "Default")
      (node (ref "DD3") (pin "4") (pinfunction "PE5_4") (pintype "passive"))
    )
    (net (code "121") (name "unconnected-(DD3C-PE6-Pad5)") (class "Default")
      (node (ref "DD3") (pin "5") (pinfunction "PE6_5") (pintype "passive"))
    )
    (net (code "122") (name "unconnected-(DD3C-PE7-Pad38)") (class "Default")
      (node (ref "DD3") (pin "38") (pinfunction "PE7_38") (pintype "passive"))
    )
    (net (code "123") (name "unconnected-(DD3C-PE8-Pad39)") (class "Default")
      (node (ref "DD3") (pin "39") (pinfunction "PE8_39") (pintype "passive"))
    )
    (net (code "124") (name "unconnected-(DD3C-PE9-Pad40)") (class "Default")
      (node (ref "DD3") (pin "40") (pinfunction "PE9_40") (pintype "passive"))
    )
    (net (code "125") (name "unconnected-(DD3C-PE10-Pad41)") (class "Default")
      (node (ref "DD3") (pin "41") (pinfunction "PE10_41") (pintype "passive"))
    )
    (net (code "126") (name "unconnected-(DD3C-PE11-Pad42)") (class "Default")
      (node (ref "DD3") (pin "42") (pinfunction "PE11_42") (pintype "passive"))
    )
    (net (code "127") (name "unconnected-(DD3C-PE12-Pad43)") (class "Default")
      (node (ref "DD3") (pin "43") (pinfunction "PE12_43") (pintype "passive"))
    )
    (net (code "128") (name "unconnected-(DD3C-PE13-Pad44)") (class "Default")
      (node (ref "DD3") (pin "44") (pinfunction "PE13_44") (pintype "passive"))
    )
    (net (code "129") (name "unconnected-(DD3C-PE14-Pad45)") (class "Default")
      (node (ref "DD3") (pin "45") (pinfunction "PE14_45") (pintype "passive"))
    )
    (net (code "130") (name "unconnected-(DD3C-PE15-Pad46)") (class "Default")
      (node (ref "DD3") (pin "46") (pinfunction "PE15_46") (pintype "passive"))
    )
    (net (code "131") (name "unconnected-(DD4-DEF-Pad8)") (class "Default")
      (node (ref "DD4") (pin "8") (pinfunction "DEF_8") (pintype "passive"))
    )
    (net (code "132") (name "unconnected-(DD4-FSW-Pad7)") (class "Default")
      (node (ref "DD4") (pin "7") (pinfunction "FSW_7") (pintype "passive"))
    )
    (net (code "133") (name "unconnected-(DD4-SW-Pad2)") (class "Default")
      (node (ref "DD4") (pin "2") (pinfunction "SW_2") (pintype "passive"))
    )
    (net (code "134") (name "unconnected-(DD4-SW-Pad3)") (class "Default")
      (node (ref "DD4") (pin "3") (pinfunction "SW_3") (pintype "passive"))
    )
    (net (code "135") (name "unconnected-(HG1-DB0-Pad7)") (class "Default")
      (node (ref "HG1") (pin "7") (pinfunction "DB0_7") (pintype "passive"))
    )
    (net (code "136") (name "unconnected-(HG1-DB1-Pad8)") (class "Default")
      (node (ref "HG1") (pin "8") (pinfunction "DB1_8") (pintype "passive"))
    )
    (net (code "137") (name "unconnected-(HG1-DB2-Pad9)") (class "Default")
      (node (ref "HG1") (pin "9") (pinfunction "DB2_9") (pintype "passive"))
    )
    (net (code "138") (name "unconnected-(HG1-DB3-Pad10)") (class "Default")
      (node (ref "HG1") (pin "10") (pinfunction "DB3_10") (pintype "passive"))
    )
    (net (code "139") (name "unconnected-(HG2-DB0-Pad7)") (class "Default")
      (node (ref "HG2") (pin "7") (pinfunction "DB0_7") (pintype "passive"))
    )
    (net (code "140") (name "unconnected-(HG2-DB1-Pad8)") (class "Default")
      (node (ref "HG2") (pin "8") (pinfunction "DB1_8") (pintype "passive"))
    )
    (net (code "141") (name "unconnected-(HG2-DB2-Pad9)") (class "Default")
      (node (ref "HG2") (pin "9") (pinfunction "DB2_9") (pintype "passive"))
    )
    (net (code "142") (name "unconnected-(HG2-DB3-Pad10)") (class "Default")
      (node (ref "HG2") (pin "10") (pinfunction "DB3_10") (pintype "passive"))
    )
  )
)
